# MKicroBUS.net
KiCad netlist of a schematic drawn in Altium Designer
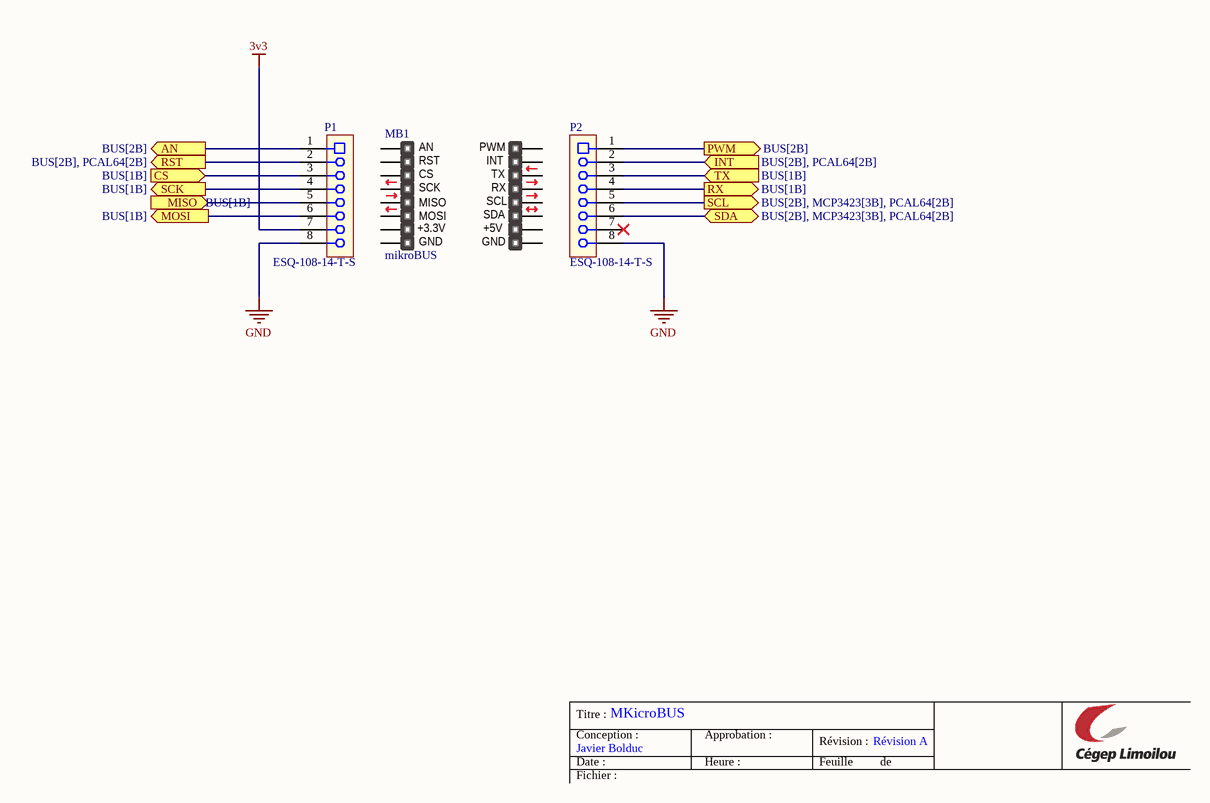
[diagram p0: MKicroBUS.schdoc]

(export (version "E")
  (design (tool "Eeschema 10.0.6"))
  (components
    (comp (ref "MB1")
      (value "mikroBUS")
      (footprint "mikroBUS-Midi-No-Connector")
      (description "mikroBUS compatible add-on board")
      (libsource (lib "TEP-AltiumLib-Modules") (part "mikroBUS compatible add-on board"))
    )
    (comp (ref "P1")
      (value "ESQ-108-14-T-S")
      (footprint "CONN_SKT_01X08_100MIL-ELEVATED-LONGPIN")
      (description "CONN SOCKET 8pos 100mils Elevated")
      (libsource (lib "TEP-AltiumLib-Connectors") (part "CONN-100MIL-SKT-01X08_ELEVATED_LONGPIN"))
    )
    (comp (ref "P2")
      (value "ESQ-108-14-T-S")
      (footprint "CONN_SKT_01X08_100MIL-ELEVATED-LONGPIN")
      (description "CONN SOCKET 8pos 100mils Elevated")
      (libsource (lib "") (part "CONN-100MIL-SKT-01X08_ELEVATED_LONGPIN_1"))
    )
  )
  (nets
    (net (code "1") (name "/AN") (class "Default")
      (node (ref "P1") (pin "1") (pinfunction "1_1") (pintype "passive"))
    )
    (net (code "2") (name "/CS") (class "Default")
      (node (ref "P1") (pin "3") (pinfunction "3_3") (pintype "passive"))
    )
    (net (code "3") (name "/INT") (class "Default")
      (node (ref "P2") (pin "2") (pinfunction "2_2") (pintype "passive"))
    )
    (net (code "4") (name "/MISO") (class "Default")
      (node (ref "P1") (pin "5") (pinfunction "5_5") (pintype "passive"))
    )
    (net (code "5") (name "/MOSI") (class "Default")
      (node (ref "P1") (pin "6") (pinfunction "6_6") (pintype "passive"))
    )
    (net (code "6") (name "/PWM") (class "Default")
      (node (ref "P2") (pin "1") (pinfunction "1_1") (pintype "passive"))
    )
    (net (code "7") (name "/RST") (class "Default")
      (node (ref "P1") (pin "2") (pinfunction "2_2") (pintype "passive"))
    )
    (net (code "8") (name "/RX") (class "Default")
      (node (ref "P2") (pin "4") (pinfunction "4_4") (pintype "passive"))
    )
    (net (code "9") (name "/SCK") (class "Default")
      (node (ref "P1") (pin "4") (pinfunction "4_4") (pintype "passive"))
    )
    (net (code "10") (name "/SCL") (class "Default")
      (node (ref "P2") (pin "5") (pinfunction "5_5") (pintype "passive"))
    )
    (net (code "11") (name "/SDA") (class "Default")
      (node (ref "P2") (pin "6") (pinfunction "6_6") (pintype "passive"))
    )
    (net (code "12") (name "/TX") (class "Default")
      (node (ref "P2") (pin "3") (pinfunction "3_3") (pintype "passive"))
    )
    (net (code "13") (name "3v3") (class "Default")
      (node (ref "P1") (pin "7") (pinfunction "7_7") (pintype "passive"))
    )
    (net (code "14") (name "GND") (class "Default")
      (node (ref "P1") (pin "8") (pinfunction "8_8") (pintype "passive"))
      (node (ref "P2") (pin "8") (pinfunction "8_8") (pintype "passive"))
    )
    (net (code "15") (name "unconnected-(MB1-3.3V-Pad7)") (class "Default")
      (node (ref "MB1") (pin "7") (pinfunction "3.3V_7") (pintype "passive"))
    )
    (net (code "16") (name "unconnected-(MB1-5V-Pad10)") (class "Default")
      (node (ref "MB1") (pin "10") (pinfunction "5V_10") (pintype "passive"))
    )
    (net (code "17") (name "unconnected-(MB1-AN-Pad1)") (class "Default")
      (node (ref "MB1") (pin "1") (pinfunction "AN_1") (pintype "passive"))
    )
    (net (code "18") (name "unconnected-(MB1-CS-Pad3)") (class "Default")
      (node (ref "MB1") (pin "3") (pinfunction "CS_3") (pintype "passive"))
    )
    (net (code "19") (name "unconnected-(MB1-GND-Pad8)") (class "Default")
      (node (ref "MB1") (pin "8") (pinfunction "GND_8") (pintype "passive"))
    )
    (net (code "20") (name "unconnected-(MB1-GND-Pad9)") (class "Default")
      (node (ref "MB1") (pin "9") (pinfunction "GND_9") (pintype "passive"))
    )
    (net (code "21") (name "unconnected-(MB1-INT-Pad15)") (class "Default")
      (node (ref "MB1") (pin "15") (pinfunction "INT_15") (pintype "passive"))
    )
    (net (code "22") (name "unconnected-(MB1-MISO-Pad5)") (class "Default")
      (node (ref "MB1") (pin "5") (pinfunction "MISO_5") (pintype "passive"))
    )
    (net (code "23") (name "unconnected-(MB1-MOSI-Pad6)") (class "Default")
      (node (ref "MB1") (pin "6") (pinfunction "MOSI_6") (pintype "passive"))
    )
    (net (code "24") (name "unconnected-(MB1-PWM-Pad16)") (class "Default")
      (node (ref "MB1") (pin "16") (pinfunction "PWM_16") (pintype "passive"))
    )
    (net (code "25") (name "unconnected-(MB1-RST-Pad2)") (class "Default")
      (node (ref "MB1") (pin "2") (pinfunction "RST_2") (pintype "passive"))
    )
    (net (code "26") (name "unconnected-(MB1-RX-Pad14)") (class "Default")
      (node (ref "MB1") (pin "14") (pinfunction "RX_14") (pintype "passive"))
    )
    (net (code "27") (name "unconnected-(MB1-SCK-Pad4)") (class "Default")
      (node (ref "MB1") (pin "4") (pinfunction "SCK_4") (pintype "passive"))
    )
    (net (code "28") (name "unconnected-(MB1-SCL-Pad12)") (class "Default")
      (node (ref "MB1") (pin "12") (pinfunction "SCL_12") (pintype "passive"))
    )
    (net (code "29") (name "unconnected-(MB1-SDA-Pad11)") (class "Default")
      (node (ref "MB1") (pin "11") (pinfunction "SDA_11") (pintype "passive"))
    )
    (net (code "30") (name "unconnected-(MB1-TX-Pad13)") (class "Default")
      (node (ref "MB1") (pin "13") (pinfunction "TX_13") (pintype "passive"))
    )
    (net (code "31") (name "unconnected-(P2-Pad7)") (class "Default")
      (node (ref "P2") (pin "7") (pinfunction "7_7") (pintype "passive+no_connect"))
    )
  )
)
